# ST-LINK.net
KiCad netlist of a schematic drawn in Altium Designer
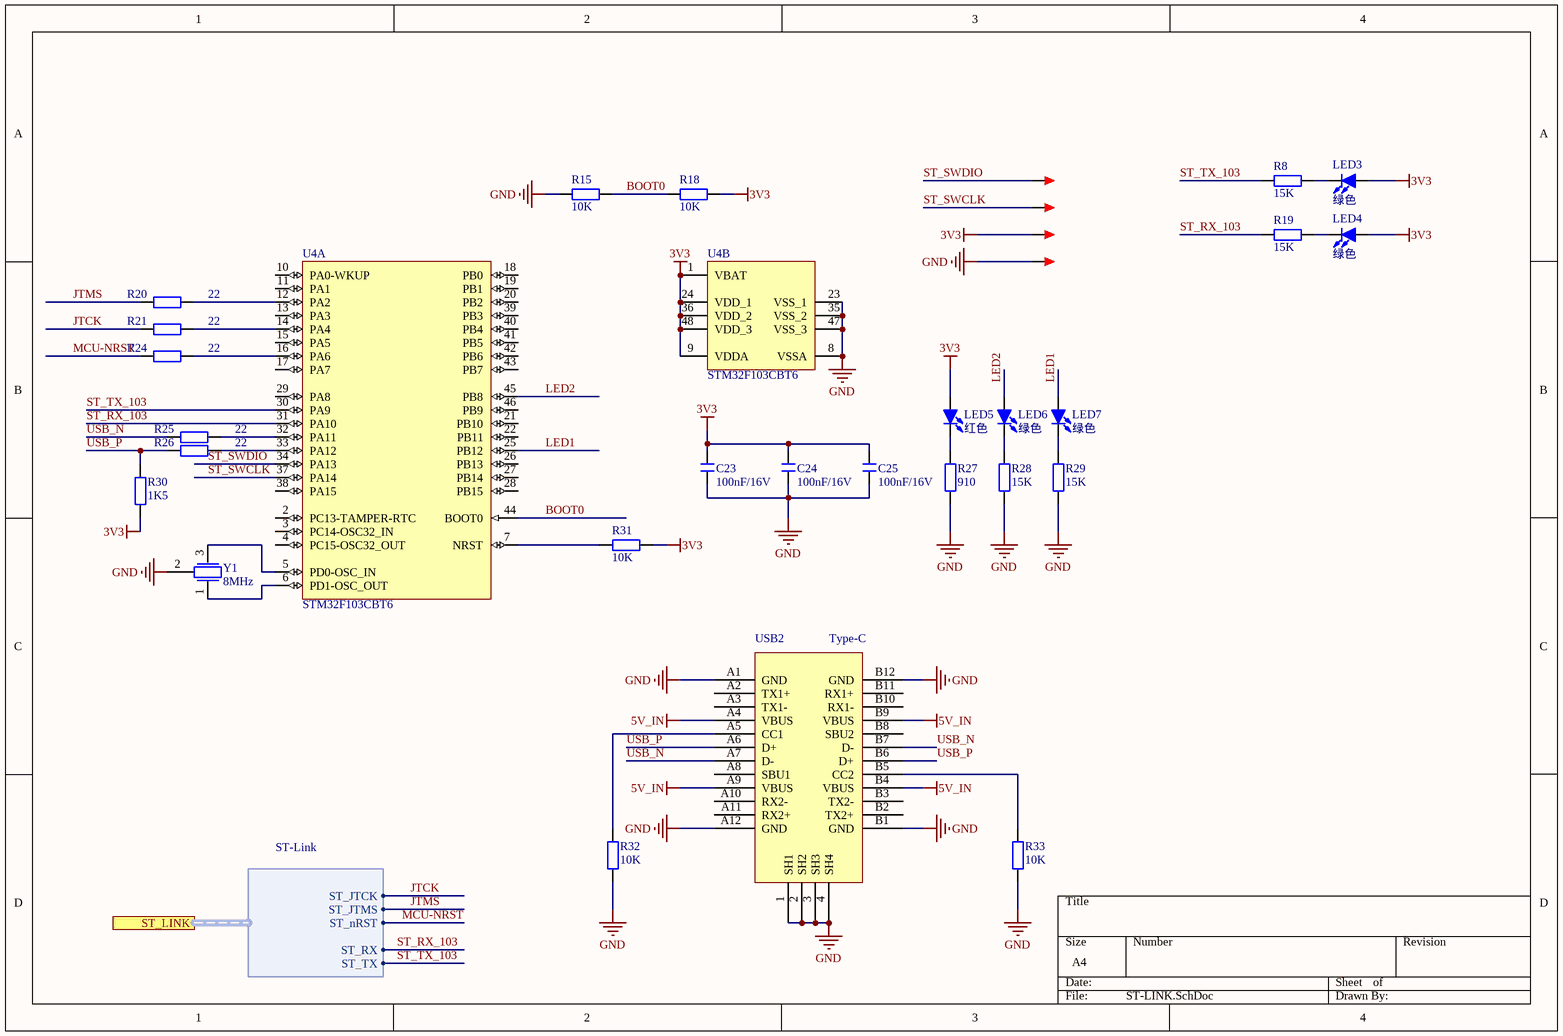
[diagram p0: ST-LINK.SchDoc]

(export (version "E")
  (design (tool "Eeschema 10.0.6"))
  (components
    (comp (ref "C23")
      (value "100nF/16V")
      (footprint "C 0402_L")
      (description "贴片电容")
      (libsource (lib "3.1   - 电阻-电容-电感") (part "C"))
    )
    (comp (ref "C24")
      (value "100nF/16V")
      (footprint "C 0402_L")
      (description "贴片电容")
      (libsource (lib "3.1   - 电阻-电容-电感") (part "C"))
    )
    (comp (ref "C25")
      (value "100nF/16V")
      (footprint "C 0402_L")
      (description "贴片电容")
      (libsource (lib "3.1   - 电阻-电容-电感") (part "C"))
    )
    (comp (ref "LED3")
      (value "绿色")
      (footprint "LED")
      (description "C84267")
      (libsource (lib "9.1   - LED") (part "LED-SMD"))
    )
    (comp (ref "LED4")
      (value "绿色")
      (footprint "LED")
      (description "C84267")
      (libsource (lib "9.1   - LED") (part "LED-SMD"))
    )
    (comp (ref "LED5")
      (value "红色")
      (footprint "LED")
      (description "C84267")
      (libsource (lib "9.1   - LED") (part "LED-SMD"))
    )
    (comp (ref "LED6")
      (value "绿色")
      (footprint "LED")
      (description "C84267")
      (libsource (lib "9.1   - LED") (part "LED-SMD"))
    )
    (comp (ref "LED7")
      (value "绿色")
      (footprint "LED")
      (description "C84267")
      (libsource (lib "9.1   - LED") (part "LED-SMD"))
    )
    (comp (ref "R8")
      (value "15K")
      (footprint "R 0402_L")
      (description "贴片电阻 0402 5%")
      (libsource (lib "3.1   - 电阻-电容-电感") (part "R"))
    )
    (comp (ref "R15")
      (value "10K")
      (footprint "R 0402_L")
      (description "贴片电阻")
      (libsource (lib "3.1   - 电阻-电容-电感") (part "R"))
    )
    (comp (ref "R18")
      (value "10K")
      (footprint "R 0402_L")
      (description "贴片电阻")
      (libsource (lib "3.1   - 电阻-电容-电感") (part "R"))
    )
    (comp (ref "R19")
      (value "15K")
      (footprint "R 0402_L")
      (description "贴片电阻 0402 5%")
      (libsource (lib "3.1   - 电阻-电容-电感") (part "R"))
    )
    (comp (ref "R20")
      (value "22")
      (footprint "R 0402_L")
      (description "贴片电阻")
      (libsource (lib "3.1   - 电阻-电容-电感") (part "R"))
    )
    (comp (ref "R21")
      (value "22")
      (footprint "R 0402_L")
      (description "贴片电阻")
      (libsource (lib "3.1   - 电阻-电容-电感") (part "R"))
    )
    (comp (ref "R24")
      (value "22")
      (footprint "R 0402_L")
      (description "贴片电阻")
      (libsource (lib "3.1   - 电阻-电容-电感") (part "R"))
    )
    (comp (ref "R25")
      (value "22")
      (footprint "R 0402_L")
      (description "贴片电阻")
      (libsource (lib "3.1   - 电阻-电容-电感") (part "R"))
    )
    (comp (ref "R26")
      (value "22")
      (footprint "R 0402_L")
      (description "贴片电阻")
      (libsource (lib "3.1   - 电阻-电容-电感") (part "R"))
    )
    (comp (ref "R27")
      (value "910")
      (footprint "R 0402_L")
      (description "贴片电阻 0402 5%")
      (libsource (lib "3.1   - 电阻-电容-电感") (part "R"))
    )
    (comp (ref "R28")
      (value "15K")
      (footprint "R 0402_L")
      (description "贴片电阻 0402 5%")
      (libsource (lib "3.1   - 电阻-电容-电感") (part "R"))
    )
    (comp (ref "R29")
      (value "15K")
      (footprint "R 0402_L")
      (description "贴片电阻 0402 5%")
      (libsource (lib "3.1   - 电阻-电容-电感") (part "R"))
    )
    (comp (ref "R30")
      (value "1K5")
      (footprint "R 0402_L")
      (description "贴片电阻")
      (libsource (lib "3.1   - 电阻-电容-电感") (part "R"))
    )
    (comp (ref "R31")
      (value "10K")
      (footprint "R 0402_L")
      (description "贴片电阻")
      (libsource (lib "3.1   - 电阻-电容-电感") (part "R"))
    )
    (comp (ref "R32")
      (value "10K")
      (footprint "R 0402_L")
      (description "贴片电阻")
      (libsource (lib "3.1   - 电阻-电容-电感") (part "R"))
    )
    (comp (ref "R33")
      (value "10K")
      (footprint "R 0402_L")
      (description "贴片电阻")
      (libsource (lib "3.1   - 电阻-电容-电感") (part "R"))
    )
    (comp (ref "TP3")
      (value "TEST")
      (footprint "TEST 1.2")
      (description "测试点")
      (libsource (lib "15.1 - 未分类器件") (part "TEST"))
    )
    (comp (ref "TP4")
      (value "TEST")
      (footprint "TEST 1.2")
      (description "测试点")
      (libsource (lib "15.1 - 未分类器件") (part "TEST"))
    )
    (comp (ref "TP5")
      (value "TEST")
      (footprint "TEST 1.2")
      (description "测试点")
      (libsource (lib "15.1 - 未分类器件") (part "TEST"))
    )
    (comp (ref "TP6")
      (value "TEST")
      (footprint "TEST 1.2")
      (description "测试点")
      (libsource (lib "15.1 - 未分类器件") (part "TEST"))
    )
    (comp (ref "U4")
      (value "STM32F103CBT6")
      (footprint "LQFP48 7X7_N")
      (libsource (lib "STMicroelectronics STM32 F1") (part "STM32F103CBT6"))
    )
    (comp (ref "USB2")
      (value "Type-C")
      (footprint "Type-c接口")
      (libsource (lib "MyPcbLib") (part "USB-Type-C-TOP"))
    )
    (comp (ref "Y1")
      (value "8MHz")
      (footprint "三脚晶振")
      (description "村田贴片")
      (libsource (lib "MyPcbLib") (part "晶振-3Pin"))
    )
  )
  (nets
    (net (code "2") (name "/BOOT0") (class "Default")
      (node (ref "R15") (pin "2") (pinfunction "2_2") (pintype "passive"))
      (node (ref "R18") (pin "2") (pinfunction "2_2") (pintype "passive"))
      (node (ref "U4") (pin "44") (pinfunction "BOOT0_44") (pintype "input"))
    )
    (net (code "3") (name "/JTCK") (class "Default")
      (node (ref "R21") (pin "2") (pinfunction "2_2") (pintype "passive"))
    )
    (net (code "4") (name "/JTMS") (class "Default")
      (node (ref "R20") (pin "2") (pinfunction "2_2") (pintype "passive"))
    )
    (net (code "5") (name "/LED1") (class "Default")
      (node (ref "LED7") (pin "1") (pinfunction "A_1") (pintype "passive"))
      (node (ref "U4") (pin "25") (pinfunction "PB12_25") (pintype "bidirectional"))
    )
    (net (code "6") (name "/LED2") (class "Default")
      (node (ref "LED6") (pin "1") (pinfunction "A_1") (pintype "passive"))
      (node (ref "U4") (pin "45") (pinfunction "PB8_45") (pintype "bidirectional"))
    )
    (net (code "7") (name "/MCU-NRST") (class "Default")
      (node (ref "R24") (pin "2") (pinfunction "2_2") (pintype "passive"))
    )
    (net (code "8") (name "/ST_RX_103") (class "Default")
      (node (ref "R19") (pin "1") (pinfunction "1_1") (pintype "passive"))
      (node (ref "U4") (pin "31") (pinfunction "PA10_31") (pintype "bidirectional"))
    )
    (net (code "9") (name "/ST_SWCLK") (class "Default")
      (node (ref "TP4") (pin "1") (pinfunction "1_1") (pintype "passive"))
      (node (ref "U4") (pin "37") (pinfunction "PA14_37") (pintype "bidirectional"))
    )
    (net (code "10") (name "/ST_SWDIO") (class "Default")
      (node (ref "TP3") (pin "1") (pinfunction "1_1") (pintype "passive"))
      (node (ref "U4") (pin "34") (pinfunction "PA13_34") (pintype "bidirectional"))
    )
    (net (code "11") (name "/ST_TX_103") (class "Default")
      (node (ref "R8") (pin "1") (pinfunction "1_1") (pintype "passive"))
      (node (ref "U4") (pin "30") (pinfunction "PA9_30") (pintype "bidirectional"))
    )
    (net (code "12") (name "/USB_N") (class "Default")
      (node (ref "R25") (pin "2") (pinfunction "2_2") (pintype "passive"))
      (node (ref "USB2") (pin "A7") (pinfunction "D-_A7") (pintype "passive"))
      (node (ref "USB2") (pin "B7") (pinfunction "D-_B7") (pintype "passive"))
    )
    (net (code "13") (name "/USB_P") (class "Default")
      (node (ref "R26") (pin "2") (pinfunction "2_2") (pintype "passive"))
      (node (ref "R30") (pin "1") (pinfunction "1_1") (pintype "passive"))
      (node (ref "USB2") (pin "A6") (pinfunction "D+_A6") (pintype "passive"))
      (node (ref "USB2") (pin "B6") (pinfunction "D+_B6") (pintype "passive"))
    )
    (net (code "15") (name "3V3") (class "Default")
      (node (ref "C23") (pin "2") (pinfunction "2_2") (pintype "passive"))
      (node (ref "C24") (pin "2") (pinfunction "2_2") (pintype "passive"))
      (node (ref "C25") (pin "2") (pinfunction "2_2") (pintype "passive"))
      (node (ref "LED3") (pin "1") (pinfunction "A_1") (pintype "passive"))
      (node (ref "LED4") (pin "1") (pinfunction "A_1") (pintype "passive"))
      (node (ref "LED5") (pin "1") (pinfunction "A_1") (pintype "passive"))
      (node (ref "R18") (pin "1") (pinfunction "1_1") (pintype "passive"))
      (node (ref "R30") (pin "2") (pinfunction "2_2") (pintype "passive"))
      (node (ref "R31") (pin "1") (pinfunction "1_1") (pintype "passive"))
      (node (ref "TP5") (pin "1") (pinfunction "1_1") (pintype "passive"))
      (node (ref "U4") (pin "1") (pinfunction "VBAT_1") (pintype "power_in"))
      (node (ref "U4") (pin "24") (pinfunction "VDD_1_24") (pintype "power_in"))
      (node (ref "U4") (pin "36") (pinfunction "VDD_2_36") (pintype "power_in"))
      (node (ref "U4") (pin "48") (pinfunction "VDD_3_48") (pintype "power_in"))
      (node (ref "U4") (pin "9") (pinfunction "VDDA_9") (pintype "power_in"))
    )
    (net (code "16") (name "5V_IN") (class "Default")
      (node (ref "USB2") (pin "A4") (pinfunction "VBUS_A4") (pintype "passive"))
      (node (ref "USB2") (pin "A9") (pinfunction "VBUS_A9") (pintype "passive"))
      (node (ref "USB2") (pin "B4") (pinfunction "VBUS_B4") (pintype "passive"))
      (node (ref "USB2") (pin "B9") (pinfunction "VBUS_B9") (pintype "passive"))
    )
    (net (code "17") (name "GND") (class "Default")
      (node (ref "C23") (pin "1") (pinfunction "1_1") (pintype "passive"))
      (node (ref "C24") (pin "1") (pinfunction "1_1") (pintype "passive"))
      (node (ref "C25") (pin "1") (pinfunction "1_1") (pintype "passive"))
      (node (ref "R15") (pin "1") (pinfunction "1_1") (pintype "passive"))
      (node (ref "R27") (pin "1") (pinfunction "1_1") (pintype "passive"))
      (node (ref "R28") (pin "1") (pinfunction "1_1") (pintype "passive"))
      (node (ref "R29") (pin "1") (pinfunction "1_1") (pintype "passive"))
      (node (ref "R32") (pin "1") (pinfunction "1_1") (pintype "passive"))
      (node (ref "R33") (pin "1") (pinfunction "1_1") (pintype "passive"))
      (node (ref "TP6") (pin "1") (pinfunction "1_1") (pintype "passive"))
      (node (ref "U4") (pin "23") (pinfunction "VSS_1_23") (pintype "power_in"))
      (node (ref "U4") (pin "35") (pinfunction "VSS_2_35") (pintype "power_in"))
      (node (ref "U4") (pin "47") (pinfunction "VSS_3_47") (pintype "power_in"))
      (node (ref "U4") (pin "8") (pinfunction "VSSA_8") (pintype "power_in"))
      (node (ref "USB2") (pin "1") (pinfunction "SH1_1") (pintype "passive"))
      (node (ref "USB2") (pin "2") (pinfunction "SH2_2") (pintype "passive"))
      (node (ref "USB2") (pin "3") (pinfunction "SH3_3") (pintype "passive"))
      (node (ref "USB2") (pin "4") (pinfunction "SH4_4") (pintype "passive"))
      (node (ref "USB2") (pin "A1") (pinfunction "GND_A1") (pintype "passive"))
      (node (ref "USB2") (pin "A12") (pinfunction "GND_A12") (pintype "passive"))
      (node (ref "USB2") (pin "B1") (pinfunction "GND_B1") (pintype "passive"))
      (node (ref "USB2") (pin "B12") (pinfunction "GND_B12") (pintype "passive"))
      (node (ref "Y1") (pin "2") (pinfunction "2_2") (pintype "passive"))
    )
    (net (code "18") (name "Net-(LED3-K)") (class "Default")
      (node (ref "LED3") (pin "2") (pinfunction "K_2") (pintype "passive"))
      (node (ref "R8") (pin "2") (pinfunction "2_2") (pintype "passive"))
    )
    (net (code "19") (name "Net-(LED4-K)") (class "Default")
      (node (ref "LED4") (pin "2") (pinfunction "K_2") (pintype "passive"))
      (node (ref "R19") (pin "2") (pinfunction "2_2") (pintype "passive"))
    )
    (net (code "20") (name "Net-(LED5-K)") (class "Default")
      (node (ref "LED5") (pin "2") (pinfunction "K_2") (pintype "passive"))
      (node (ref "R27") (pin "2") (pinfunction "2_2") (pintype "passive"))
    )
    (net (code "21") (name "Net-(LED6-K)") (class "Default")
      (node (ref "LED6") (pin "2") (pinfunction "K_2") (pintype "passive"))
      (node (ref "R28") (pin "2") (pinfunction "2_2") (pintype "passive"))
    )
    (net (code "22") (name "Net-(LED7-K)") (class "Default")
      (node (ref "LED7") (pin "2") (pinfunction "K_2") (pintype "passive"))
      (node (ref "R29") (pin "2") (pinfunction "2_2") (pintype "passive"))
    )
    (net (code "23") (name "Net-(U4A-NRST)") (class "Default")
      (node (ref "R31") (pin "2") (pinfunction "2_2") (pintype "passive"))
      (node (ref "U4") (pin "7") (pinfunction "NRST_7") (pintype "bidirectional"))
    )
    (net (code "24") (name "Net-(U4A-PA2)") (class "Default")
      (node (ref "R20") (pin "1") (pinfunction "1_1") (pintype "passive"))
      (node (ref "U4") (pin "12") (pinfunction "PA2_12") (pintype "bidirectional"))
    )
    (net (code "25") (name "Net-(U4A-PA4)") (class "Default")
      (node (ref "R21") (pin "1") (pinfunction "1_1") (pintype "passive"))
      (node (ref "U4") (pin "14") (pinfunction "PA4_14") (pintype "bidirectional"))
    )
    (net (code "26") (name "Net-(U4A-PA6)") (class "Default")
      (node (ref "R24") (pin "1") (pinfunction "1_1") (pintype "passive"))
      (node (ref "U4") (pin "16") (pinfunction "PA6_16") (pintype "bidirectional"))
    )
    (net (code "27") (name "Net-(U4A-PA11)") (class "Default")
      (node (ref "R25") (pin "1") (pinfunction "1_1") (pintype "passive"))
      (node (ref "U4") (pin "32") (pinfunction "PA11_32") (pintype "bidirectional"))
    )
    (net (code "28") (name "Net-(U4A-PA12)") (class "Default")
      (node (ref "R26") (pin "1") (pinfunction "1_1") (pintype "passive"))
      (node (ref "U4") (pin "33") (pinfunction "PA12_33") (pintype "bidirectional"))
    )
    (net (code "29") (name "Net-(U4A-PD0-OSC_IN)") (class "Default")
      (node (ref "U4") (pin "5") (pinfunction "PD0-OSC_IN_5") (pintype "bidirectional"))
      (node (ref "Y1") (pin "3") (pinfunction "3_3") (pintype "passive"))
    )
    (net (code "30") (name "Net-(U4A-PD1-OSC_OUT)") (class "Default")
      (node (ref "U4") (pin "6") (pinfunction "PD1-OSC_OUT_6") (pintype "bidirectional"))
      (node (ref "Y1") (pin "1") (pinfunction "1_1") (pintype "passive"))
    )
    (net (code "31") (name "Net-(USB2-CC1)") (class "Default")
      (node (ref "R32") (pin "2") (pinfunction "2_2") (pintype "passive"))
      (node (ref "USB2") (pin "A5") (pinfunction "CC1_A5") (pintype "passive"))
    )
    (net (code "32") (name "Net-(USB2-CC2)") (class "Default")
      (node (ref "R33") (pin "2") (pinfunction "2_2") (pintype "passive"))
      (node (ref "USB2") (pin "B5") (pinfunction "CC2_B5") (pintype "passive"))
    )
    (net (code "33") (name "unconnected-(U4A-PA0-WKUP-Pad10)") (class "Default")
      (node (ref "U4") (pin "10") (pinfunction "PA0-WKUP_10") (pintype "bidirectional"))
    )
    (net (code "34") (name "unconnected-(U4A-PA1-Pad11)") (class "Default")
      (node (ref "U4") (pin "11") (pinfunction "PA1_11") (pintype "bidirectional"))
    )
    (net (code "35") (name "unconnected-(U4A-PA3-Pad13)") (class "Default")
      (node (ref "U4") (pin "13") (pinfunction "PA3_13") (pintype "bidirectional"))
    )
    (net (code "36") (name "unconnected-(U4A-PA5-Pad15)") (class "Default")
      (node (ref "U4") (pin "15") (pinfunction "PA5_15") (pintype "bidirectional"))
    )
    (net (code "37") (name "unconnected-(U4A-PA7-Pad17)") (class "Default")
      (node (ref "U4") (pin "17") (pinfunction "PA7_17") (pintype "bidirectional"))
    )
    (net (code "38") (name "unconnected-(U4A-PA8-Pad29)") (class "Default")
      (node (ref "U4") (pin "29") (pinfunction "PA8_29") (pintype "bidirectional"))
    )
    (net (code "39") (name "unconnected-(U4A-PA15-Pad38)") (class "Default")
      (node (ref "U4") (pin "38") (pinfunction "PA15_38") (pintype "bidirectional"))
    )
    (net (code "40") (name "unconnected-(U4A-PB0-Pad18)") (class "Default")
      (node (ref "U4") (pin "18") (pinfunction "PB0_18") (pintype "bidirectional"))
    )
    (net (code "41") (name "unconnected-(U4A-PB1-Pad19)") (class "Default")
      (node (ref "U4") (pin "19") (pinfunction "PB1_19") (pintype "bidirectional"))
    )
    (net (code "42") (name "unconnected-(U4A-PB2-Pad20)") (class "Default")
      (node (ref "U4") (pin "20") (pinfunction "PB2_20") (pintype "bidirectional"))
    )
    (net (code "43") (name "unconnected-(U4A-PB3-Pad39)") (class "Default")
      (node (ref "U4") (pin "39") (pinfunction "PB3_39") (pintype "bidirectional"))
    )
    (net (code "44") (name "unconnected-(U4A-PB4-Pad40)") (class "Default")
      (node (ref "U4") (pin "40") (pinfunction "PB4_40") (pintype "bidirectional"))
    )
    (net (code "45") (name "unconnected-(U4A-PB5-Pad41)") (class "Default")
      (node (ref "U4") (pin "41") (pinfunction "PB5_41") (pintype "bidirectional"))
    )
    (net (code "46") (name "unconnected-(U4A-PB6-Pad42)") (class "Default")
      (node (ref "U4") (pin "42") (pinfunction "PB6_42") (pintype "bidirectional"))
    )
    (net (code "47") (name "unconnected-(U4A-PB7-Pad43)") (class "Default")
      (node (ref "U4") (pin "43") (pinfunction "PB7_43") (pintype "bidirectional"))
    )
    (net (code "48") (name "unconnected-(U4A-PB9-Pad46)") (class "Default")
      (node (ref "U4") (pin "46") (pinfunction "PB9_46") (pintype "bidirectional"))
    )
    (net (code "49") (name "unconnected-(U4A-PB10-Pad21)") (class "Default")
      (node (ref "U4") (pin "21") (pinfunction "PB10_21") (pintype "bidirectional"))
    )
    (net (code "50") (name "unconnected-(U4A-PB11-Pad22)") (class "Default")
      (node (ref "U4") (pin "22") (pinfunction "PB11_22") (pintype "bidirectional"))
    )
    (net (code "51") (name "unconnected-(U4A-PB13-Pad26)") (class "Default")
      (node (ref "U4") (pin "26") (pinfunction "PB13_26") (pintype "bidirectional"))
    )
    (net (code "52") (name "unconnected-(U4A-PB14-Pad27)") (class "Default")
      (node (ref "U4") (pin "27") (pinfunction "PB14_27") (pintype "bidirectional"))
    )
    (net (code "53") (name "unconnected-(U4A-PB15-Pad28)") (class "Default")
      (node (ref "U4") (pin "28") (pinfunction "PB15_28") (pintype "bidirectional"))
    )
    (net (code "54") (name "unconnected-(U4A-PC13-TAMPER-RTC-Pad2)") (class "Default")
      (node (ref "U4") (pin "2") (pinfunction "PC13-TAMPER-RTC_2") (pintype "bidirectional"))
    )
    (net (code "55") (name "unconnected-(U4A-PC14-OSC32_IN-Pad3)") (class "Default")
      (node (ref "U4") (pin "3") (pinfunction "PC14-OSC32_IN_3") (pintype "bidirectional"))
    )
    (net (code "56") (name "unconnected-(U4A-PC15-OSC32_OUT-Pad4)") (class "Default")
      (node (ref "U4") (pin "4") (pinfunction "PC15-OSC32_OUT_4") (pintype "bidirectional"))
    )
    (net (code "57") (name "unconnected-(USB2-RX1+-PadB11)") (class "Default")
      (node (ref "USB2") (pin "B11") (pinfunction "RX1+_B11") (pintype "passive"))
    )
    (net (code "58") (name "unconnected-(USB2-RX1--PadB10)") (class "Default")
      (node (ref "USB2") (pin "B10") (pinfunction "RX1-_B10") (pintype "passive"))
    )
    (net (code "59") (name "unconnected-(USB2-RX2+-PadA11)") (class "Default")
      (node (ref "USB2") (pin "A11") (pinfunction "RX2+_A11") (pintype "passive"))
    )
    (net (code "60") (name "unconnected-(USB2-RX2--PadA10)") (class "Default")
      (node (ref "USB2") (pin "A10") (pinfunction "RX2-_A10") (pintype "passive"))
    )
    (net (code "61") (name "unconnected-(USB2-SBU1-PadA8)") (class "Default")
      (node (ref "USB2") (pin "A8") (pinfunction "SBU1_A8") (pintype "passive"))
    )
    (net (code "62") (name "unconnected-(USB2-SBU2-PadB8)") (class "Default")
      (node (ref "USB2") (pin "B8") (pinfunction "SBU2_B8") (pintype "passive"))
    )
    (net (code "63") (name "unconnected-(USB2-TX1+-PadA2)") (class "Default")
      (node (ref "USB2") (pin "A2") (pinfunction "TX1+_A2") (pintype "passive"))
    )
    (net (code "64") (name "unconnected-(USB2-TX1--PadA3)") (class "Default")
      (node (ref "USB2") (pin "A3") (pinfunction "TX1-_A3") (pintype "passive"))
    )
    (net (code "65") (name "unconnected-(USB2-TX2+-PadB2)") (class "Default")
      (node (ref "USB2") (pin "B2") (pinfunction "TX2+_B2") (pintype "passive"))
    )
    (net (code "66") (name "unconnected-(USB2-TX2--PadB3)") (class "Default")
      (node (ref "USB2") (pin "B3") (pinfunction "TX2-_B3") (pintype "passive"))
    )
  )
)
